# schCambiennhietdotestboard.net
KiCad netlist of a schematic drawn in Altium Designer
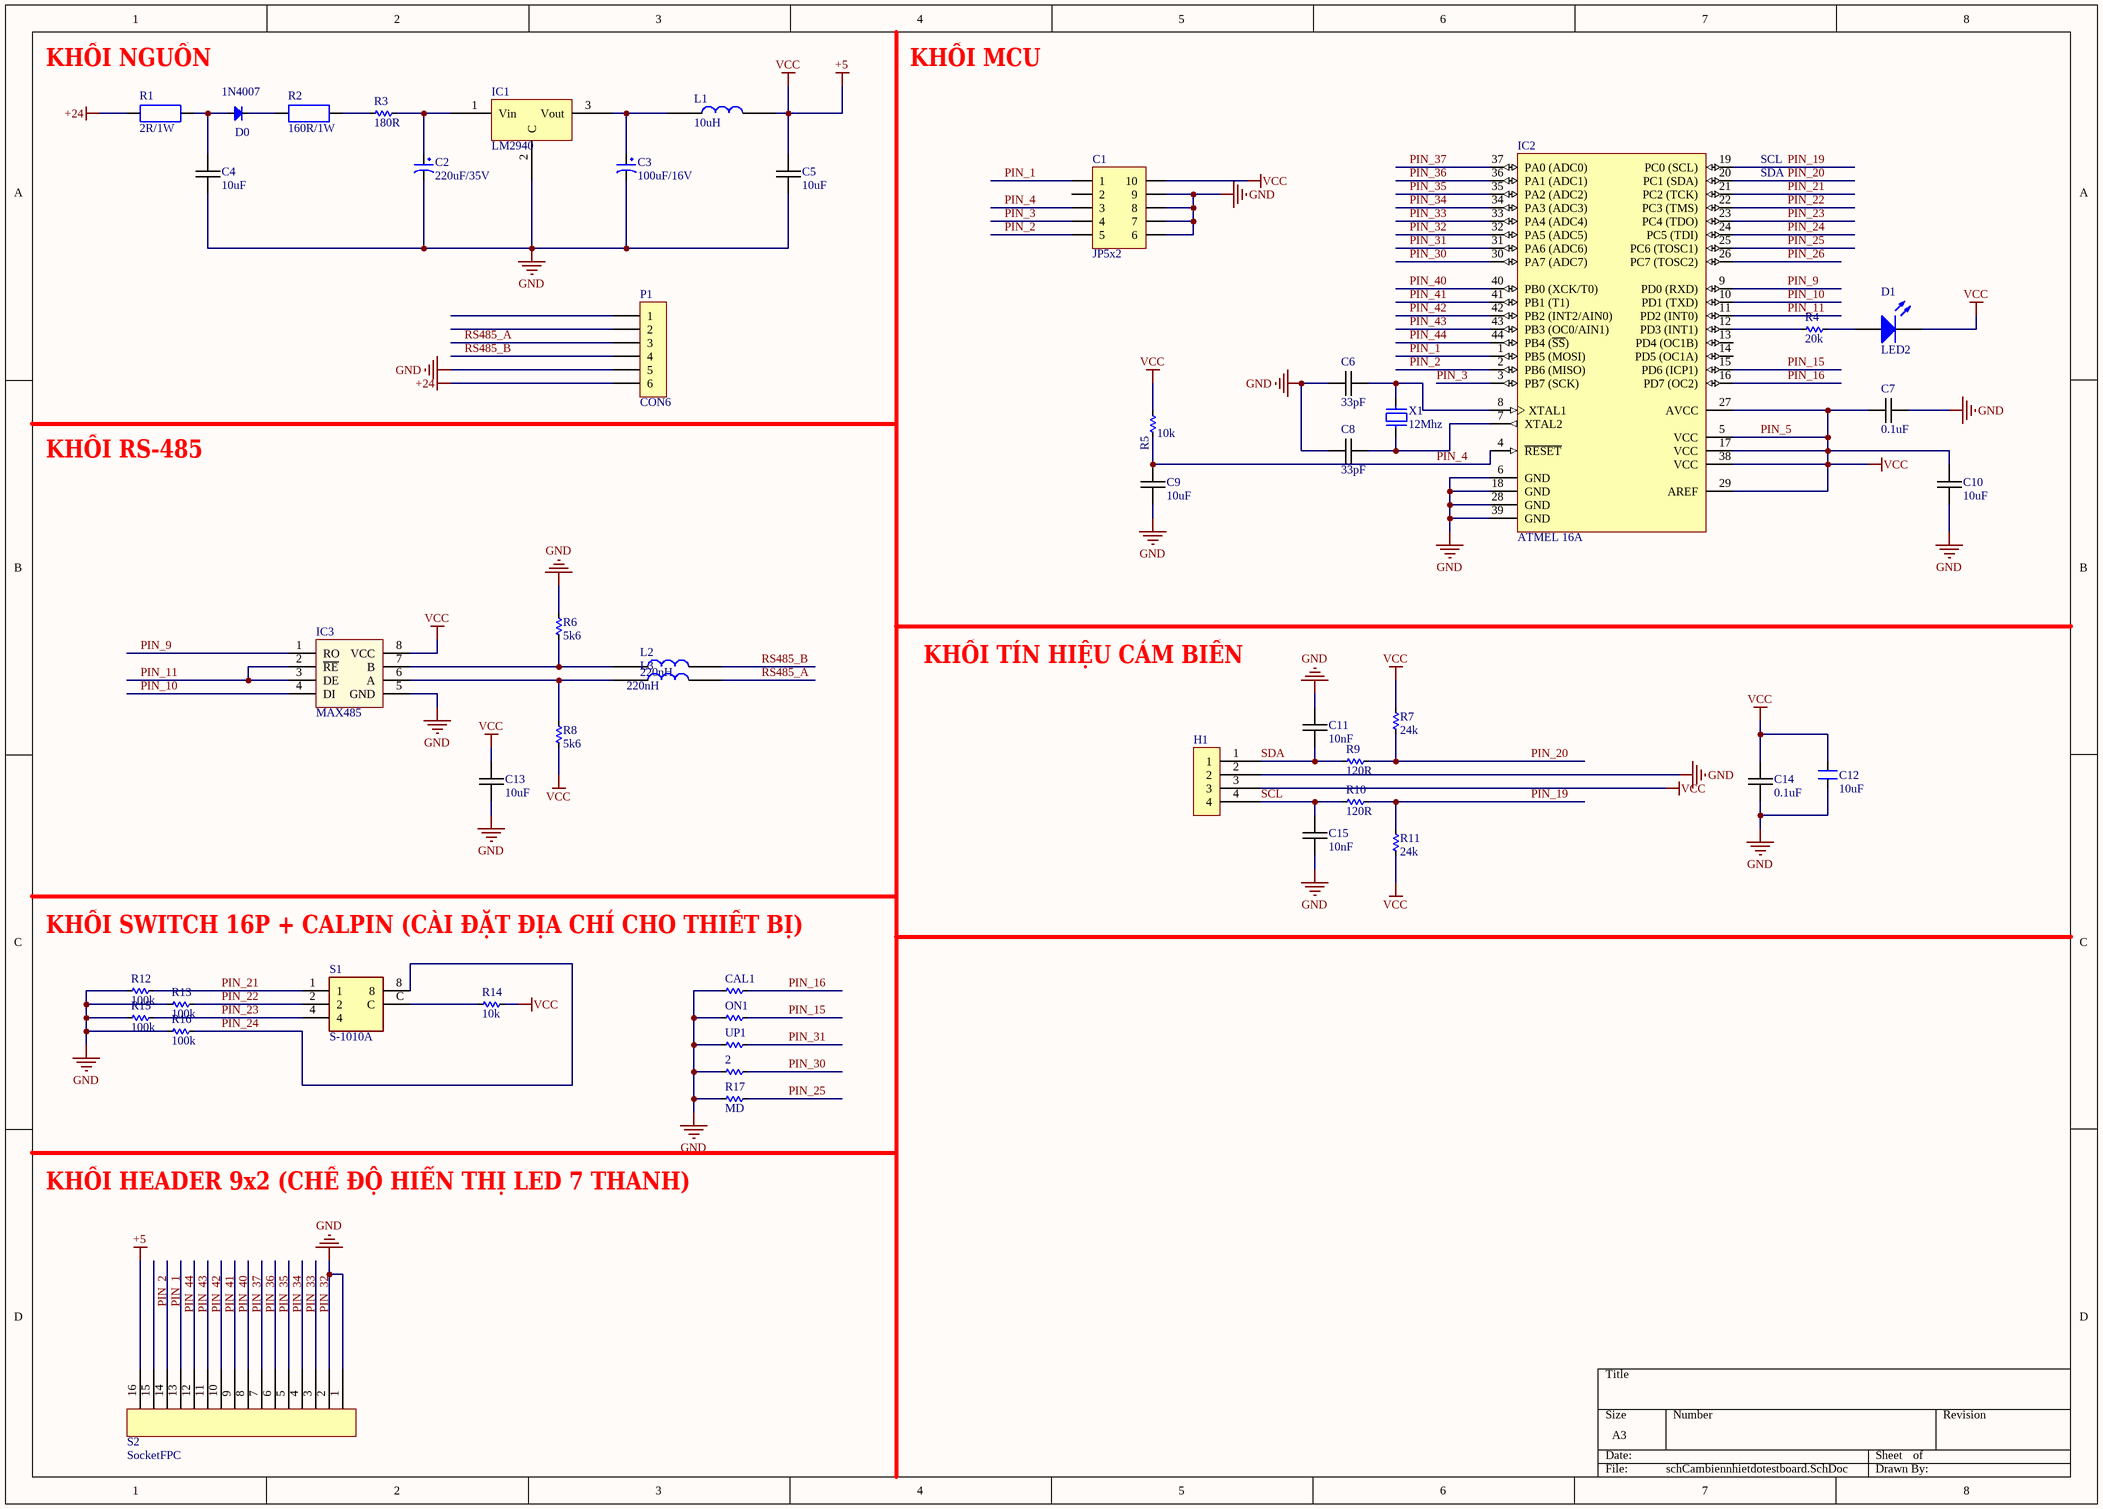
[diagram p0: schCambiennhietdotestboard.SchDoc]

(export (version "E")
  (design (tool "Eeschema 10.0.6"))
  (components
    (comp (ref "2")
      (value "0R")
      (footprint "RES-SMD-0805")
      (description "Resistor")
      (fields
        (field (name "MANUFACTURER") "Generic Components")
        (field (name "PUBLISHER") "Altium Hobart Technology Centre")
      )
      (libsource (lib "LIBRARY") (part "Res-SMD"))
    )
    (comp (ref "C1")
      (value "JP5x2")
      (footprint "JP5-D2T")
      (description "WR-PHD 2.54 mm Dual Socket Header")
      (fields
        (field (name "MANUFACTURER") "Würth Elektronik eiSos GmbH")
        (field (name "PARTNO") "61301021821")
        (field (name "CREATED BY") "Karrer Zheng")
      )
      (libsource (lib "LIBRARY") (part "JP5x2"))
    )
    (comp (ref "C2")
      (value "220uF/35V")
      (footprint "CP1.5/3.4")
      (description "Cap 100uF/35V - 470uF/16V")
      (libsource (lib "syhaunguyen") (part "CP3"))
    )
    (comp (ref "C3")
      (value "100uF/16V")
      (footprint "CP1/2")
      (description "Cap P  0,1uF < 22uF , 16 - 50V")
      (libsource (lib "syhaunguyen") (part "CP1"))
    )
    (comp (ref "C4")
      (value "10uF")
      (footprint "SM-Cap-1206")
      (description "GENERIC CAPACITOR NON POLARISED 1206")
      (fields
        (field (name "MANUFACTURER PART NUMBER") "GMK316F106ZL-T")
        (field (name "MANUFACTURER") "Taiyo Yuden")
      )
      (libsource (lib "vh_altium_library") (part "1206C-10U-35V-X7R"))
    )
    (comp (ref "C5")
      (value "10uF")
      (footprint "SM-CAP-0805")
      (description "CAPACITOR 0805 CERAMIC")
      (libsource (lib "vh_altium_library") (part "0805C-10UF-25V-X5R-SAM"))
    )
    (comp (ref "C6")
      (value "33pF")
      (footprint "CN-SMD-0805")
      (description "GENERIC CAPACITOR NON POLARISED 1206")
      (fields
        (field (name "MANUFACTURER PART NUMBER") "GMK316F106ZL-T")
        (field (name "MANUFACTURER") "Taiyo Yuden")
      )
      (libsource (lib "vh_altium_library") (part "1206C-10U-35V-X7R"))
    )
    (comp (ref "C7")
      (value "0.1uF")
      (footprint "CN-SMD-0805")
      (description "GENERIC CAPACITOR NON POLARISED 1206")
      (fields
        (field (name "MANUFACTURER PART NUMBER") "GMK316F106ZL-T")
        (field (name "MANUFACTURER") "Taiyo Yuden")
      )
      (libsource (lib "vh_altium_library") (part "1206C-10U-35V-X7R"))
    )
    (comp (ref "C8")
      (value "33pF")
      (footprint "CN-SMD-0805")
      (description "GENERIC CAPACITOR NON POLARISED 1206")
      (fields
        (field (name "MANUFACTURER PART NUMBER") "GMK316F106ZL-T")
        (field (name "MANUFACTURER") "Taiyo Yuden")
      )
      (libsource (lib "vh_altium_library") (part "1206C-10U-35V-X7R"))
    )
    (comp (ref "C9")
      (value "10uF")
      (footprint "CN-SMD-0805")
      (description "GENERIC CAPACITOR NON POLARISED 1206")
      (fields
        (field (name "MANUFACTURER PART NUMBER") "GMK316F106ZL-T")
        (field (name "MANUFACTURER") "Taiyo Yuden")
      )
      (libsource (lib "vh_altium_library") (part "1206C-10U-35V-X7R"))
    )
    (comp (ref "C10")
      (value "10uF")
      (footprint "CN-SMD-0805")
      (description "GENERIC CAPACITOR NON POLARISED 1206")
      (fields
        (field (name "MANUFACTURER PART NUMBER") "GMK316F106ZL-T")
        (field (name "MANUFACTURER") "Taiyo Yuden")
      )
      (libsource (lib "vh_altium_library") (part "1206C-10U-35V-X7R"))
    )
    (comp (ref "C11")
      (value "10nF")
      (footprint "CN-SMD-0805")
      (description "GENERIC CAPACITOR NON POLARISED 1206")
      (fields
        (field (name "MANUFACTURER PART NUMBER") "GMK316F106ZL-T")
        (field (name "MANUFACTURER") "Taiyo Yuden")
      )
      (libsource (lib "vh_altium_library") (part "1206C-10U-35V-X7R"))
    )
    (comp (ref "C12")
      (value "10uF")
      (footprint "SM-Cap-1206")
      (description "Cap SMD")
      (libsource (lib "Cty1") (part "CM"))
    )
    (comp (ref "C13")
      (value "10uF")
      (footprint "CN-SMD-0805")
      (description "GENERIC CAPACITOR NON POLARISED 1206")
      (fields
        (field (name "MANUFACTURER PART NUMBER") "GMK316F106ZL-T")
        (field (name "MANUFACTURER") "Taiyo Yuden")
      )
      (libsource (lib "vh_altium_library") (part "1206C-10U-35V-X7R"))
    )
    (comp (ref "C14")
      (value "0.1uF")
      (footprint "CN-SMD-0805")
      (description "GENERIC CAPACITOR NON POLARISED 1206")
      (fields
        (field (name "MANUFACTURER PART NUMBER") "GMK316F106ZL-T")
        (field (name "MANUFACTURER") "Taiyo Yuden")
      )
      (libsource (lib "vh_altium_library") (part "1206C-10U-35V-X7R"))
    )
    (comp (ref "C15")
      (value "10nF")
      (footprint "CN-SMD-0805")
      (description "GENERIC CAPACITOR NON POLARISED 1206")
      (fields
        (field (name "MANUFACTURER PART NUMBER") "GMK316F106ZL-T")
        (field (name "MANUFACTURER") "Taiyo Yuden")
      )
      (libsource (lib "vh_altium_library") (part "1206C-10U-35V-X7R"))
    )
    (comp (ref "CAL1")
      (value "0R")
      (footprint "RES-SMD-0805")
      (description "Resistor")
      (fields
        (field (name "MANUFACTURER") "Generic Components")
        (field (name "PUBLISHER") "Altium Hobart Technology Centre")
      )
      (libsource (lib "LIBRARY") (part "Res-SMD"))
    )
    (comp (ref "D0")
      (value "1N4007")
      (footprint "DIO-SMD-106")
      (description "Default Diode")
      (fields (field (name "PUBLISHER") "Altium Limited"))
      (libsource (lib "LIBRARY") (part "Diode SMD"))
    )
    (comp (ref "D1")
      (value "LED2")
      (footprint "LED-0805-Red")
      (description "Typical RED, GREEN, YELLOW, AMBER GaAs LED")
      (fields (field (name "PUBLISHER") "Altium Limited"))
      (libsource (lib "Miscellaneous Devices") (part "LED2"))
    )
    (comp (ref "H1")
      (value "Header4P")
      (footprint "PCBComponent_1")
      (libsource (lib "schLibHeader4P") (part "HEADER4_PIN"))
    )
    (comp (ref "IC1") (value "LM2940") (footprint "QTO-220") (libsource (lib "schLibTL-780") (part "TL-780")))
    (comp (ref "IC2")
      (value "ATMEL 16A")
      (footprint "TQFP 44")
      (libsource (lib "LIBRARY") (part "ATmega16A-AU"))
    )
    (comp (ref "IC3")
      (value "MAX485")
      (footprint "SO-8")
      (description "RS232 - RS485 (Same sn75176)")
      (libsource (lib "LIBRARY") (part "MAX485"))
    )
    (comp (ref "L1") (value "10uH") (footprint "RES-1WD") (libsource (lib "Inductor1210") (part "L")))
    (comp (ref "L2") (value "220nH") (footprint "RES-SMD-0805") (libsource (lib "Inductor1210") (part "L")))
    (comp (ref "L3") (value "220nH") (footprint "RES-SMD-0805") (libsource (lib "Inductor1210") (part "L")))
    (comp (ref "ON1")
      (value "0R")
      (footprint "RES-SMD-0805")
      (description "Resistor")
      (fields
        (field (name "MANUFACTURER") "Generic Components")
        (field (name "PUBLISHER") "Altium Hobart Technology Centre")
      )
      (libsource (lib "LIBRARY") (part "Res-SMD"))
    )
    (comp (ref "P1")
      (value "CON6")
      (footprint "4plus2PKF350")
      (description "Connector")
      (libsource (lib "Cty1") (part "CON6"))
    )
    (comp (ref "R1")
      (value "2R/1W")
      (footprint "R2WD")
      (description "Resistor 2W")
      (libsource (lib "syhaunguyen") (part "R2W"))
    )
    (comp (ref "R2")
      (value "160R/1W")
      (footprint "R2WD")
      (description "Resistor 2W")
      (libsource (lib "syhaunguyen") (part "R2W"))
    )
    (comp (ref "R3")
      (value "180R")
      (footprint "RES-SMD-2512")
      (description "Resistor")
      (fields
        (field (name "MANUFACTURER") "Generic Components")
        (field (name "PUBLISHER") "Altium Hobart Technology Centre")
      )
      (libsource (lib "LIBRARY") (part "Res-SMD"))
    )
    (comp (ref "R4")
      (value "20k")
      (footprint "RES-SMD-0805")
      (description "Resistor")
      (fields
        (field (name "MANUFACTURER") "Generic Components")
        (field (name "PUBLISHER") "Altium Hobart Technology Centre")
      )
      (libsource (lib "LIBRARY") (part "Res-SMD"))
    )
    (comp (ref "R5")
      (value "10k")
      (footprint "RES-SMD-0805")
      (description "Resistor")
      (fields
        (field (name "MANUFACTURER") "Generic Components")
        (field (name "PUBLISHER") "Altium Hobart Technology Centre")
      )
      (libsource (lib "LIBRARY") (part "Res-SMD"))
    )
    (comp (ref "R6")
      (value "5k6")
      (footprint "RES-SMD-0805")
      (description "Resistor")
      (fields
        (field (name "MANUFACTURER") "Generic Components")
        (field (name "PUBLISHER") "Altium Hobart Technology Centre")
      )
      (libsource (lib "LIBRARY") (part "Res-SMD"))
    )
    (comp (ref "R7")
      (value "24k")
      (footprint "RES-SMD-0805")
      (description "Resistor")
      (fields
        (field (name "MANUFACTURER") "Generic Components")
        (field (name "PUBLISHER") "Altium Hobart Technology Centre")
      )
      (libsource (lib "LIBRARY") (part "Res-SMD"))
    )
    (comp (ref "R8")
      (value "5k6")
      (footprint "RES-SMD-0805")
      (description "Resistor")
      (fields
        (field (name "MANUFACTURER") "Generic Components")
        (field (name "PUBLISHER") "Altium Hobart Technology Centre")
      )
      (libsource (lib "LIBRARY") (part "Res-SMD"))
    )
    (comp (ref "R9")
      (value "120R")
      (footprint "RES-SMD-0805")
      (description "Resistor")
      (fields
        (field (name "MANUFACTURER") "Generic Components")
        (field (name "PUBLISHER") "Altium Hobart Technology Centre")
      )
      (libsource (lib "LIBRARY") (part "Res-SMD"))
    )
    (comp (ref "R10")
      (value "120R")
      (footprint "RES-SMD-0805")
      (description "Resistor")
      (fields
        (field (name "MANUFACTURER") "Generic Components")
        (field (name "PUBLISHER") "Altium Hobart Technology Centre")
      )
      (libsource (lib "LIBRARY") (part "Res-SMD"))
    )
    (comp (ref "R11")
      (value "24k")
      (footprint "RES-SMD-0805")
      (description "Resistor")
      (fields
        (field (name "MANUFACTURER") "Generic Components")
        (field (name "PUBLISHER") "Altium Hobart Technology Centre")
      )
      (libsource (lib "LIBRARY") (part "Res-SMD"))
    )
    (comp (ref "R12")
      (value "100k")
      (footprint "RES-SMD-0805")
      (description "Resistor")
      (fields
        (field (name "MANUFACTURER") "Generic Components")
        (field (name "PUBLISHER") "Altium Hobart Technology Centre")
      )
      (libsource (lib "LIBRARY") (part "Res-SMD"))
    )
    (comp (ref "R13")
      (value "100k")
      (footprint "RES-SMD-0805")
      (description "Resistor")
      (fields
        (field (name "MANUFACTURER") "Generic Components")
        (field (name "PUBLISHER") "Altium Hobart Technology Centre")
      )
      (libsource (lib "LIBRARY") (part "Res-SMD"))
    )
    (comp (ref "R14")
      (value "10k")
      (footprint "RES-SMD-0805")
      (description "Resistor")
      (fields
        (field (name "MANUFACTURER") "Generic Components")
        (field (name "PUBLISHER") "Altium Hobart Technology Centre")
      )
      (libsource (lib "LIBRARY") (part "Res-SMD"))
    )
    (comp (ref "R15")
      (value "100k")
      (footprint "RES-SMD-0805")
      (description "Resistor")
      (fields
        (field (name "MANUFACTURER") "Generic Components")
        (field (name "PUBLISHER") "Altium Hobart Technology Centre")
      )
      (libsource (lib "LIBRARY") (part "Res-SMD"))
    )
    (comp (ref "R16")
      (value "100k")
      (footprint "RES-SMD-0805")
      (description "Resistor")
      (fields
        (field (name "MANUFACTURER") "Generic Components")
        (field (name "PUBLISHER") "Altium Hobart Technology Centre")
      )
      (libsource (lib "LIBRARY") (part "Res-SMD"))
    )
    (comp (ref "R17")
      (value "MD")
      (footprint "RES-SMD-0805")
      (description "Resistor")
      (fields
        (field (name "MANUFACTURER") "Generic Components")
        (field (name "PUBLISHER") "Altium Hobart Technology Centre")
      )
      (libsource (lib "LIBRARY") (part "Res-SMD"))
    )
    (comp (ref "S1")
      (value "S-1010A")
      (footprint "A-1010S")
      (description "Switch")
      (fields (field (name "RS PART NUMBER") "3524666"))
      (libsource (lib "SamacSys") (part "S-1010A"))
    )
    (comp (ref "S2")
      (value "SocketFPC")
      (footprint "FPC16P-0.5")
      (description "Socket FPC 16P 0.5mm")
      (libsource (lib "FPC16P") (part "FPC16P"))
    )
    (comp (ref "UP1")
      (value "0R")
      (footprint "RES-SMD-0805")
      (description "Resistor")
      (fields
        (field (name "MANUFACTURER") "Generic Components")
        (field (name "PUBLISHER") "Altium Hobart Technology Centre")
      )
      (libsource (lib "LIBRARY") (part "Res-SMD"))
    )
    (comp (ref "X1")
      (value "12Mhz")
      (footprint "XTAL49S-SMD")
      (description "Crystal, 32.768 KHz, -40 to 85 degC, 3.2 x 1.5 x 0.9 mm SMD")
      (libsource (lib "LIBRARY") (part "XT2"))
    )
  )
  (nets
    (net (code "1") (name "+5") (class "Default")
      (node (ref "C1") (pin "10") (pinfunction "10_10") (pintype "passive"))
      (node (ref "C10") (pin "1") (pintype "passive"))
      (node (ref "C12") (pin "2") (pinfunction "2_2") (pintype "passive"))
      (node (ref "C13") (pin "1") (pintype "passive"))
      (node (ref "C14") (pin "1") (pintype "passive"))
      (node (ref "C5") (pin "1") (pintype "passive"))
      (node (ref "C7") (pin "1") (pintype "passive"))
      (node (ref "D1") (pin "2") (pinfunction "K_2") (pintype "passive"))
      (node (ref "H1") (pin "3") (pinfunction "3_3") (pintype "passive"))
      (node (ref "IC2") (pin "17") (pinfunction "VCC_17") (pintype "power_in"))
      (node (ref "IC2") (pin "27") (pinfunction "AVCC_27") (pintype "power_in"))
      (node (ref "IC2") (pin "29") (pinfunction "AREF_29") (pintype "power_in"))
      (node (ref "IC2") (pin "38") (pinfunction "VCC_38") (pintype "power_in"))
      (node (ref "IC2") (pin "5") (pinfunction "VCC_5") (pintype "power_in"))
      (node (ref "IC3") (pin "8") (pinfunction "VCC_8") (pintype "passive"))
      (node (ref "L1") (pin "2") (pinfunction "2_2") (pintype "passive"))
      (node (ref "R11") (pin "1") (pinfunction "1_1") (pintype "passive"))
      (node (ref "R14") (pin "1") (pinfunction "1_1") (pintype "passive"))
      (node (ref "R5") (pin "1") (pinfunction "1_1") (pintype "passive"))
      (node (ref "R7") (pin "1") (pinfunction "1_1") (pintype "passive"))
      (node (ref "R8") (pin "2") (pinfunction "2_2") (pintype "passive"))
      (node (ref "S2") (pin "16") (pinfunction "16_16") (pintype "passive"))
    )
    (net (code "2") (name "+24") (class "Default")
      (node (ref "P1") (pin "6") (pinfunction "6_6") (pintype "passive"))
      (node (ref "R1") (pin "2") (pinfunction "2_2") (pintype "passive"))
    )
    (net (code "3") (name "/PIN_1") (class "Default")
      (node (ref "C1") (pin "1") (pinfunction "1_1") (pintype "passive"))
      (node (ref "IC2") (pin "1") (pinfunction "PB5_(MOSI)_1") (pintype "bidirectional"))
      (node (ref "S2") (pin "14") (pinfunction "14_14") (pintype "passive"))
    )
    (net (code "4") (name "/PIN_2") (class "Default")
      (node (ref "C1") (pin "5") (pinfunction "5_5") (pintype "passive"))
      (node (ref "IC2") (pin "2") (pinfunction "PB6_(MISO)_2") (pintype "bidirectional"))
      (node (ref "S2") (pin "15") (pinfunction "15_15") (pintype "passive"))
    )
    (net (code "5") (name "/PIN_3") (class "Default")
      (node (ref "C1") (pin "4") (pinfunction "4_4") (pintype "passive"))
      (node (ref "IC2") (pin "3") (pinfunction "PB7_(SCK)_3") (pintype "bidirectional"))
    )
    (net (code "6") (name "/PIN_4") (class "Default")
      (node (ref "C1") (pin "3") (pinfunction "3_3") (pintype "passive"))
      (node (ref "C9") (pin "1") (pintype "passive"))
      (node (ref "IC2") (pin "4") (pinfunction "~{RESET}_4") (pintype "input"))
      (node (ref "R5") (pin "2") (pinfunction "2_2") (pintype "passive"))
    )
    (net (code "7") (name "/PIN_9") (class "Default")
      (node (ref "IC2") (pin "9") (pinfunction "PD0_(RXD)_9") (pintype "bidirectional"))
      (node (ref "IC3") (pin "1") (pinfunction "RO_1") (pintype "passive"))
    )
    (net (code "8") (name "/PIN_10") (class "Default")
      (node (ref "IC2") (pin "10") (pinfunction "PD1_(TXD)_10") (pintype "bidirectional"))
      (node (ref "IC3") (pin "4") (pinfunction "DI_4") (pintype "passive"))
    )
    (net (code "9") (name "/PIN_11") (class "Default")
      (node (ref "IC2") (pin "11") (pinfunction "PD2_(INT0)_11") (pintype "bidirectional"))
      (node (ref "IC3") (pin "2") (pinfunction "~{RE}_2") (pintype "passive"))
      (node (ref "IC3") (pin "3") (pinfunction "DE_3") (pintype "passive"))
    )
    (net (code "10") (name "/PIN_15") (class "Default")
      (node (ref "IC2") (pin "15") (pinfunction "PD6_(ICP1)_15") (pintype "bidirectional"))
      (node (ref "ON1") (pin "1") (pinfunction "1_1") (pintype "passive"))
    )
    (net (code "11") (name "/PIN_16") (class "Default")
      (node (ref "CAL1") (pin "1") (pinfunction "1_1") (pintype "passive"))
      (node (ref "IC2") (pin "16") (pinfunction "PD7_(OC2)_16") (pintype "bidirectional"))
    )
    (net (code "12") (name "/PIN_19") (class "Default")
      (node (ref "IC2") (pin "19") (pinfunction "PC0_(SCL)_19") (pintype "bidirectional"))
      (node (ref "R10") (pin "1") (pinfunction "1_1") (pintype "passive"))
      (node (ref "R11") (pin "2") (pinfunction "2_2") (pintype "passive"))
    )
    (net (code "13") (name "/PIN_20") (class "Default")
      (node (ref "IC2") (pin "20") (pinfunction "PC1_(SDA)_20") (pintype "bidirectional"))
      (node (ref "R7") (pin "2") (pinfunction "2_2") (pintype "passive"))
      (node (ref "R9") (pin "2") (pinfunction "2_2") (pintype "passive"))
    )
    (net (code "14") (name "/PIN_21") (class "Default")
      (node (ref "IC2") (pin "21") (pinfunction "PC2_(TCK)_21") (pintype "bidirectional"))
      (node (ref "R12") (pin "2") (pinfunction "2_2") (pintype "passive"))
      (node (ref "S1") (pin "1") (pinfunction "1_1") (pintype "passive"))
    )
    (net (code "15") (name "/PIN_22") (class "Default")
      (node (ref "IC2") (pin "22") (pinfunction "PC3_(TMS)_22") (pintype "bidirectional"))
      (node (ref "R13") (pin "2") (pinfunction "2_2") (pintype "passive"))
      (node (ref "S1") (pin "2") (pinfunction "2_2") (pintype "passive"))
    )
    (net (code "16") (name "/PIN_23") (class "Default")
      (node (ref "IC2") (pin "23") (pinfunction "PC4_(TDO)_23") (pintype "bidirectional"))
      (node (ref "R15") (pin "2") (pinfunction "2_2") (pintype "passive"))
      (node (ref "S1") (pin "4") (pinfunction "4_4") (pintype "passive"))
    )
    (net (code "17") (name "/PIN_24") (class "Default")
      (node (ref "IC2") (pin "24") (pinfunction "PC5_(TDI)_24") (pintype "bidirectional"))
      (node (ref "R16") (pin "2") (pinfunction "2_2") (pintype "passive"))
      (node (ref "S1") (pin "8") (pinfunction "8_8") (pintype "passive"))
    )
    (net (code "18") (name "/PIN_25") (class "Default")
      (node (ref "IC2") (pin "25") (pinfunction "PC6_(TOSC1)_25") (pintype "bidirectional"))
      (node (ref "R17") (pin "1") (pinfunction "1_1") (pintype "passive"))
    )
    (net (code "19") (name "/PIN_26") (class "Default")
      (node (ref "IC2") (pin "26") (pinfunction "PC7_(TOSC2)_26") (pintype "bidirectional"))
    )
    (net (code "20") (name "/PIN_30") (class "Default")
      (node (ref "2") (pin "1") (pinfunction "1_1") (pintype "passive"))
      (node (ref "IC2") (pin "30") (pinfunction "PA7_(ADC7)_30") (pintype "bidirectional"))
    )
    (net (code "21") (name "/PIN_31") (class "Default")
      (node (ref "IC2") (pin "31") (pinfunction "PA6_(ADC6)_31") (pintype "bidirectional"))
      (node (ref "UP1") (pin "1") (pinfunction "1_1") (pintype "passive"))
    )
    (net (code "22") (name "/PIN_32") (class "Default")
      (node (ref "IC2") (pin "32") (pinfunction "PA5_(ADC5)_32") (pintype "bidirectional"))
      (node (ref "S2") (pin "3") (pinfunction "3_3") (pintype "passive"))
    )
    (net (code "23") (name "/PIN_33") (class "Default")
      (node (ref "IC2") (pin "33") (pinfunction "PA4_(ADC4)_33") (pintype "bidirectional"))
      (node (ref "S2") (pin "4") (pinfunction "4_4") (pintype "passive"))
    )
    (net (code "24") (name "/PIN_34") (class "Default")
      (node (ref "IC2") (pin "34") (pinfunction "PA3_(ADC3)_34") (pintype "bidirectional"))
      (node (ref "S2") (pin "5") (pinfunction "5_5") (pintype "passive"))
    )
    (net (code "25") (name "/PIN_35") (class "Default")
      (node (ref "IC2") (pin "35") (pinfunction "PA2_(ADC2)_35") (pintype "bidirectional"))
      (node (ref "S2") (pin "6") (pinfunction "6_6") (pintype "passive"))
    )
    (net (code "26") (name "/PIN_36") (class "Default")
      (node (ref "IC2") (pin "36") (pinfunction "PA1_(ADC1)_36") (pintype "bidirectional"))
      (node (ref "S2") (pin "7") (pinfunction "7_7") (pintype "passive"))
    )
    (net (code "27") (name "/PIN_37") (class "Default")
      (node (ref "IC2") (pin "37") (pinfunction "PA0_(ADC0)_37") (pintype "bidirectional"))
      (node (ref "S2") (pin "8") (pinfunction "8_8") (pintype "passive"))
    )
    (net (code "28") (name "/PIN_40") (class "Default")
      (node (ref "IC2") (pin "40") (pinfunction "PB0_(XCK/T0)_40") (pintype "bidirectional"))
      (node (ref "S2") (pin "9") (pinfunction "9_9") (pintype "passive"))
    )
    (net (code "29") (name "/PIN_41") (class "Default")
      (node (ref "IC2") (pin "41") (pinfunction "PB1_(T1)_41") (pintype "bidirectional"))
      (node (ref "S2") (pin "10") (pinfunction "10_10") (pintype "passive"))
    )
    (net (code "30") (name "/PIN_42") (class "Default")
      (node (ref "IC2") (pin "42") (pinfunction "PB2_(INT2/AIN0)_42") (pintype "bidirectional"))
      (node (ref "S2") (pin "11") (pinfunction "11_11") (pintype "passive"))
    )
    (net (code "31") (name "/PIN_43") (class "Default")
      (node (ref "IC2") (pin "43") (pinfunction "PB3_(OC0/AIN1)_43") (pintype "bidirectional"))
      (node (ref "S2") (pin "12") (pinfunction "12_12") (pintype "passive"))
    )
    (net (code "32") (name "/PIN_44") (class "Default")
      (node (ref "IC2") (pin "44") (pinfunction "PB4_(~{SS})_44") (pintype "bidirectional"))
      (node (ref "S2") (pin "13") (pinfunction "13_13") (pintype "passive"))
    )
    (net (code "33") (name "/RS485_A") (class "Default")
      (node (ref "L3") (pin "2") (pinfunction "2_2") (pintype "passive"))
      (node (ref "P1") (pin "3") (pinfunction "3_3") (pintype "passive"))
    )
    (net (code "34") (name "/RS485_B") (class "Default")
      (node (ref "L2") (pin "2") (pinfunction "2_2") (pintype "passive"))
      (node (ref "P1") (pin "4") (pinfunction "4_4") (pintype "passive"))
    )
    (net (code "35") (name "/SCL") (class "Default")
      (node (ref "C15") (pin "2") (pintype "passive"))
      (node (ref "H1") (pin "4") (pinfunction "4_4") (pintype "passive"))
      (node (ref "R10") (pin "2") (pinfunction "2_2") (pintype "passive"))
    )
    (net (code "36") (name "/SDA") (class "Default")
      (node (ref "C11") (pin "2") (pintype "passive"))
      (node (ref "H1") (pin "1") (pinfunction "1_1") (pintype "passive"))
      (node (ref "R9") (pin "1") (pinfunction "1_1") (pintype "passive"))
    )
    (net (code "37") (name "GND") (class "Default")
      (node (ref "2") (pin "2") (pinfunction "2_2") (pintype "passive"))
      (node (ref "C1") (pin "6") (pinfunction "6_6") (pintype "passive"))
      (node (ref "C1") (pin "7") (pinfunction "7_7") (pintype "passive"))
      (node (ref "C1") (pin "8") (pinfunction "8_8") (pintype "passive"))
      (node (ref "C1") (pin "9") (pinfunction "9_9") (pintype "passive"))
      (node (ref "C10") (pin "2") (pintype "passive"))
      (node (ref "C11") (pin "1") (pintype "passive"))
      (node (ref "C12") (pin "1") (pinfunction "1_1") (pintype "passive"))
      (node (ref "C13") (pin "2") (pintype "passive"))
      (node (ref "C14") (pin "2") (pintype "passive"))
      (node (ref "C15") (pin "1") (pintype "passive"))
      (node (ref "C2") (pin "2") (pinfunction "2_2") (pintype "passive"))
      (node (ref "C3") (pin "2") (pinfunction "2_2") (pintype "passive"))
      (node (ref "C4") (pin "2") (pintype "passive"))
      (node (ref "C5") (pin "2") (pintype "passive"))
      (node (ref "C6") (pin "1") (pintype "passive"))
      (node (ref "C7") (pin "2") (pintype "passive"))
      (node (ref "C8") (pin "1") (pintype "passive"))
      (node (ref "C9") (pin "2") (pintype "passive"))
      (node (ref "CAL1") (pin "2") (pinfunction "2_2") (pintype "passive"))
      (node (ref "H1") (pin "2") (pinfunction "2_2") (pintype "passive"))
      (node (ref "IC1") (pin "2") (pinfunction "C_2") (pintype "passive"))
      (node (ref "IC2") (pin "18") (pinfunction "GND_18") (pintype "power_in"))
      (node (ref "IC2") (pin "28") (pinfunction "GND_28") (pintype "power_in"))
      (node (ref "IC2") (pin "39") (pinfunction "GND_39") (pintype "power_in"))
      (node (ref "IC2") (pin "6") (pinfunction "GND_6") (pintype "power_in"))
      (node (ref "IC3") (pin "5") (pinfunction "GND_5") (pintype "passive"))
      (node (ref "ON1") (pin "2") (pinfunction "2_2") (pintype "passive"))
      (node (ref "P1") (pin "5") (pinfunction "5_5") (pintype "passive"))
      (node (ref "R12") (pin "1") (pinfunction "1_1") (pintype "passive"))
      (node (ref "R13") (pin "1") (pinfunction "1_1") (pintype "passive"))
      (node (ref "R15") (pin "1") (pinfunction "1_1") (pintype "passive"))
      (node (ref "R16") (pin "1") (pinfunction "1_1") (pintype "passive"))
      (node (ref "R17") (pin "2") (pinfunction "2_2") (pintype "passive"))
      (node (ref "R6") (pin "1") (pinfunction "1_1") (pintype "passive"))
      (node (ref "S2") (pin "1") (pinfunction "1_1") (pintype "passive"))
      (node (ref "S2") (pin "2") (pinfunction "2_2") (pintype "passive"))
      (node (ref "UP1") (pin "2") (pinfunction "2_2") (pintype "passive"))
    )
    (net (code "38") (name "Net-(D0-A)") (class "Default")
      (node (ref "C4") (pin "1") (pintype "passive"))
      (node (ref "D0") (pin "1") (pinfunction "A_1") (pintype "passive"))
      (node (ref "R1") (pin "1") (pinfunction "1_1") (pintype "passive"))
    )
    (net (code "39") (name "Net-(D0-K)") (class "Default")
      (node (ref "D0") (pin "2") (pinfunction "K_2") (pintype "passive"))
      (node (ref "R2") (pin "2") (pinfunction "2_2") (pintype "passive"))
    )
    (net (code "40") (name "Net-(D1-A)") (class "Default")
      (node (ref "D1") (pin "1") (pinfunction "A_1") (pintype "passive"))
      (node (ref "R4") (pin "2") (pinfunction "2_2") (pintype "passive"))
    )
    (net (code "41") (name "Net-(IC1-Vin)") (class "Default")
      (node (ref "C2") (pin "1") (pinfunction "1_1") (pintype "passive"))
      (node (ref "IC1") (pin "1") (pinfunction "Vin_1") (pintype "passive"))
      (node (ref "R3") (pin "1") (pinfunction "1_1") (pintype "passive"))
    )
    (net (code "42") (name "Net-(IC1-Vout)") (class "Default")
      (node (ref "C3") (pin "1") (pinfunction "1_1") (pintype "passive"))
      (node (ref "IC1") (pin "3") (pinfunction "Vout_3") (pintype "passive"))
      (node (ref "L1") (pin "1") (pinfunction "1_1") (pintype "passive"))
    )
    (net (code "43") (name "Net-(IC2-PD3_(INT1))") (class "Default")
      (node (ref "IC2") (pin "12") (pinfunction "PD3_(INT1)_12") (pintype "bidirectional"))
      (node (ref "R4") (pin "1") (pinfunction "1_1") (pintype "passive"))
    )
    (net (code "44") (name "Net-(IC2-XTAL1)") (class "Default")
      (node (ref "C6") (pin "2") (pintype "passive"))
      (node (ref "IC2") (pin "8") (pinfunction "XTAL1_8") (pintype "input"))
      (node (ref "X1") (pin "2") (pinfunction "2_2") (pintype "passive"))
    )
    (net (code "45") (name "Net-(IC2-XTAL2)") (class "Default")
      (node (ref "C8") (pin "2") (pintype "passive"))
      (node (ref "IC2") (pin "7") (pinfunction "XTAL2_7") (pintype "output"))
      (node (ref "X1") (pin "1") (pinfunction "1_1") (pintype "passive"))
    )
    (net (code "46") (name "Net-(IC3-A)") (class "Default")
      (node (ref "IC3") (pin "6") (pinfunction "A_6") (pintype "passive"))
      (node (ref "L3") (pin "1") (pinfunction "1_1") (pintype "passive"))
      (node (ref "R8") (pin "1") (pinfunction "1_1") (pintype "passive"))
    )
    (net (code "47") (name "Net-(IC3-B)") (class "Default")
      (node (ref "IC3") (pin "7") (pinfunction "B_7") (pintype "passive"))
      (node (ref "L2") (pin "1") (pinfunction "1_1") (pintype "passive"))
      (node (ref "R6") (pin "2") (pinfunction "2_2") (pintype "passive"))
    )
    (net (code "48") (name "Net-(R2-Pad1)") (class "Default")
      (node (ref "R2") (pin "1") (pinfunction "1_1") (pintype "passive"))
      (node (ref "R3") (pin "2") (pinfunction "2_2") (pintype "passive"))
    )
    (net (code "49") (name "Net-(R14-Pad2)") (class "Default")
      (node (ref "R14") (pin "2") (pinfunction "2_2") (pintype "passive"))
      (node (ref "S1") (pin "C") (pinfunction "C_C") (pintype "passive"))
    )
    (net (code "50") (name "unconnected-(C1-Pad2)") (class "Default")
      (node (ref "C1") (pin "2") (pinfunction "2_2") (pintype "passive"))
    )
    (net (code "51") (name "unconnected-(IC2-PD4_(OC1B)-Pad13)") (class "Default")
      (node (ref "IC2") (pin "13") (pinfunction "PD4_(OC1B)_13") (pintype "bidirectional"))
    )
    (net (code "52") (name "unconnected-(IC2-PD5_(OC1A)-Pad14)") (class "Default")
      (node (ref "IC2") (pin "14") (pinfunction "PD5_(OC1A)_14") (pintype "bidirectional"))
    )
    (net (code "53") (name "unconnected-(P1-Pad1)") (class "Default")
      (node (ref "P1") (pin "1") (pinfunction "1_1") (pintype "passive"))
    )
    (net (code "54") (name "unconnected-(P1-Pad2)") (class "Default")
      (node (ref "P1") (pin "2") (pinfunction "2_2") (pintype "passive"))
    )
  )
)
